# drive-mp1907.net
KiCad netlist of a schematic drawn in Altium Designer
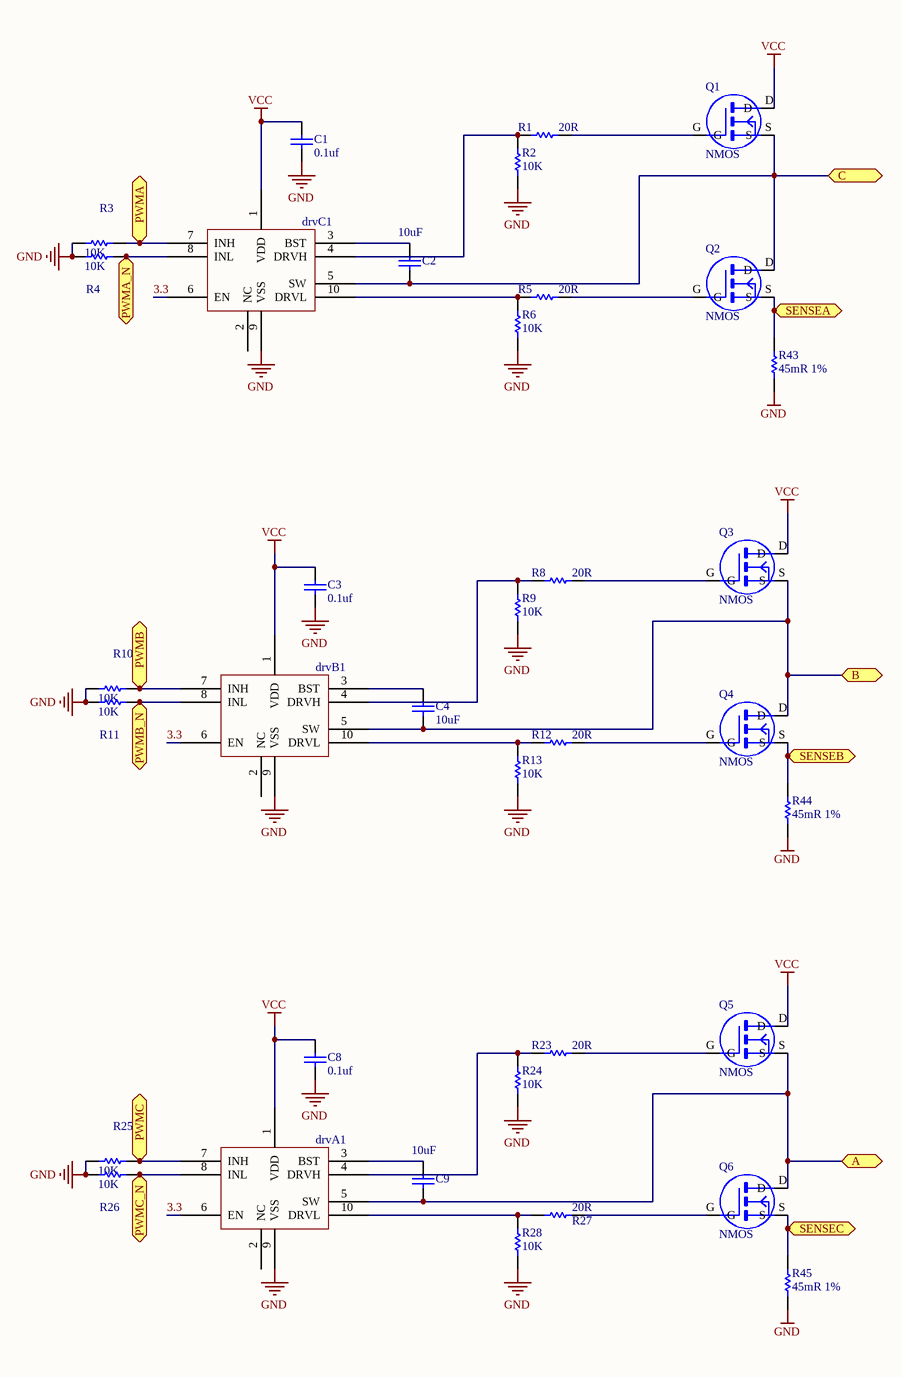
[diagram p0: drive-mp1907.SchDoc]

(export (version "E")
  (design (tool "Eeschema 10.0.6"))
  (components
    (comp (ref "C1")
      (value "0.1uf")
      (footprint "0603")
      (description "Capacitor")
      (fields (field (name "Comment") "Cap") (field (name "PUBLISHER") "Altium Limited"))
      (libsource (lib "PCB_Project") (part "Cap"))
    )
    (comp (ref "C2")
      (value "10uF")
      (footprint "0805")
      (description "Capacitor")
      (fields (field (name "PUBLISHER") "Altium Limited"))
      (libsource (lib "PCB_Project") (part "Cap"))
    )
    (comp (ref "C3")
      (value "0.1uf")
      (footprint "0603")
      (description "Capacitor")
      (fields (field (name "Comment") "Cap") (field (name "PUBLISHER") "Altium Limited"))
      (libsource (lib "PCB_Project") (part "Cap"))
    )
    (comp (ref "C4")
      (value "10uF")
      (footprint "0805")
      (description "Capacitor")
      (fields (field (name "Comment") "Cap") (field (name "PUBLISHER") "Altium Limited"))
      (libsource (lib "PCB_Project") (part "Cap"))
    )
    (comp (ref "C8")
      (value "0.1uf")
      (footprint "0603")
      (description "Capacitor")
      (fields (field (name "Comment") "Cap") (field (name "PUBLISHER") "Altium Limited"))
      (libsource (lib "PCB_Project") (part "Cap"))
    )
    (comp (ref "C9")
      (value "10uF")
      (footprint "0805")
      (description "Capacitor")
      (fields (field (name "PUBLISHER") "Altium Limited"))
      (libsource (lib "PCB_Project") (part "Cap"))
    )
    (comp (ref "drvA1") (value "MP1907") (footprint "MP1907") (libsource (lib "PCB_Project") (part "MP1907")))
    (comp (ref "drvB1") (value "MP1907") (footprint "MP1907") (libsource (lib "PCB_Project") (part "MP1907")))
    (comp (ref "drvC1") (value "MP1907") (footprint "MP1907") (libsource (lib "PCB_Project") (part "MP1907")))
    (comp (ref "Q1") (value "NMOS") (footprint "BSC025N03MS") (libsource (lib "PCB_Project") (part "NMOS")))
    (comp (ref "Q2") (value "NMOS") (footprint "BSC025N03MS") (libsource (lib "PCB_Project") (part "NMOS")))
    (comp (ref "Q3") (value "NMOS") (footprint "BSC025N03MS") (libsource (lib "PCB_Project") (part "NMOS")))
    (comp (ref "Q4") (value "NMOS") (footprint "BSC025N03MS") (libsource (lib "PCB_Project") (part "NMOS")))
    (comp (ref "Q5") (value "NMOS") (footprint "BSC025N03MS") (libsource (lib "PCB_Project") (part "NMOS")))
    (comp (ref "Q6") (value "NMOS") (footprint "BSC025N03MS") (libsource (lib "PCB_Project") (part "NMOS")))
    (comp (ref "R1")
      (value "20R")
      (footprint "0603")
      (description "Resistor")
      (fields (field (name "Comment") "Res1") (field (name "PUBLISHER") "Altium Limited"))
      (libsource (lib "Miscellaneous Devices") (part "Res1"))
    )
    (comp (ref "R2")
      (value "10K")
      (footprint "0603")
      (description "Resistor")
      (fields (field (name "Comment") "Res1") (field (name "PUBLISHER") "Altium Limited"))
      (libsource (lib "Miscellaneous Devices") (part "Res1"))
    )
    (comp (ref "R3")
      (value "10K")
      (footprint "0603")
      (description "Resistor")
      (fields (field (name "Comment") "Res1") (field (name "PUBLISHER") "Altium Limited"))
      (libsource (lib "Miscellaneous Devices") (part "Res1"))
    )
    (comp (ref "R4")
      (value "10K")
      (footprint "0603")
      (description "Resistor")
      (fields (field (name "Comment") "Res1") (field (name "PUBLISHER") "Altium Limited"))
      (libsource (lib "Miscellaneous Devices") (part "Res1"))
    )
    (comp (ref "R5")
      (value "20R")
      (footprint "0603")
      (description "Resistor")
      (fields (field (name "Comment") "Res1") (field (name "PUBLISHER") "Altium Limited"))
      (libsource (lib "Miscellaneous Devices") (part "Res1"))
    )
    (comp (ref "R6")
      (value "10K")
      (footprint "0603")
      (description "Resistor")
      (fields (field (name "Comment") "Res1") (field (name "PUBLISHER") "Altium Limited"))
      (libsource (lib "Miscellaneous Devices") (part "Res1"))
    )
    (comp (ref "R8")
      (value "20R")
      (footprint "0603")
      (description "Resistor")
      (fields (field (name "Comment") "Res1") (field (name "PUBLISHER") "Altium Limited"))
      (libsource (lib "Miscellaneous Devices") (part "Res1"))
    )
    (comp (ref "R9")
      (value "10K")
      (footprint "0603")
      (description "Resistor")
      (fields (field (name "Comment") "Res1") (field (name "PUBLISHER") "Altium Limited"))
      (libsource (lib "Miscellaneous Devices") (part "Res1"))
    )
    (comp (ref "R10")
      (value "10K")
      (footprint "0603")
      (description "Resistor")
      (fields (field (name "Comment") "Res1") (field (name "PUBLISHER") "Altium Limited"))
      (libsource (lib "Miscellaneous Devices") (part "Res1"))
    )
    (comp (ref "R11")
      (value "10K")
      (footprint "0603")
      (description "Resistor")
      (fields (field (name "Comment") "Res1") (field (name "PUBLISHER") "Altium Limited"))
      (libsource (lib "Miscellaneous Devices") (part "Res1"))
    )
    (comp (ref "R12")
      (value "20R")
      (footprint "0603")
      (description "Resistor")
      (fields (field (name "Comment") "Res1") (field (name "PUBLISHER") "Altium Limited"))
      (libsource (lib "Miscellaneous Devices") (part "Res1"))
    )
    (comp (ref "R13")
      (value "10K")
      (footprint "0603")
      (description "Resistor")
      (fields (field (name "Comment") "Res1") (field (name "PUBLISHER") "Altium Limited"))
      (libsource (lib "Miscellaneous Devices") (part "Res1"))
    )
    (comp (ref "R23")
      (value "20R")
      (footprint "0603")
      (description "Resistor")
      (fields (field (name "Comment") "Res1") (field (name "PUBLISHER") "Altium Limited"))
      (libsource (lib "Miscellaneous Devices") (part "Res1"))
    )
    (comp (ref "R24")
      (value "10K")
      (footprint "0603")
      (description "Resistor")
      (fields (field (name "Comment") "Res1") (field (name "PUBLISHER") "Altium Limited"))
      (libsource (lib "Miscellaneous Devices") (part "Res1"))
    )
    (comp (ref "R25")
      (value "10K")
      (footprint "0603")
      (description "Resistor")
      (fields (field (name "Comment") "Res1") (field (name "PUBLISHER") "Altium Limited"))
      (libsource (lib "Miscellaneous Devices") (part "Res1"))
    )
    (comp (ref "R26")
      (value "10K")
      (footprint "0603")
      (description "Resistor")
      (fields (field (name "Comment") "Res1") (field (name "PUBLISHER") "Altium Limited"))
      (libsource (lib "Miscellaneous Devices") (part "Res1"))
    )
    (comp (ref "R27")
      (value "20R")
      (footprint "0603")
      (description "Resistor")
      (fields (field (name "Comment") "Res1") (field (name "PUBLISHER") "Altium Limited"))
      (libsource (lib "Miscellaneous Devices") (part "Res1"))
    )
    (comp (ref "R28")
      (value "10K")
      (footprint "0603")
      (description "Resistor")
      (fields (field (name "Comment") "Res1") (field (name "PUBLISHER") "Altium Limited"))
      (libsource (lib "Miscellaneous Devices") (part "Res1"))
    )
    (comp (ref "R43")
      (value "45mR 1%")
      (footprint "2512")
      (description "Resistor")
      (fields (field (name "PUBLISHER") "Altium Limited"))
      (libsource (lib "Miscellaneous Devices") (part "Res1"))
    )
    (comp (ref "R44")
      (value "45mR 1%")
      (footprint "2512")
      (description "Resistor")
      (fields (field (name "PUBLISHER") "Altium Limited"))
      (libsource (lib "Miscellaneous Devices") (part "Res1"))
    )
    (comp (ref "R45")
      (value "45mR 1%")
      (footprint "2512")
      (description "Resistor")
      (fields (field (name "PUBLISHER") "Altium Limited"))
      (libsource (lib "Miscellaneous Devices") (part "Res1"))
    )
  )
  (nets
    (net (code "1") (name "/3.3") (class "Default")
      (node (ref "drvA1") (pin "6") (pinfunction "EN_6") (pintype "passive"))
      (node (ref "drvB1") (pin "6") (pinfunction "EN_6") (pintype "passive"))
      (node (ref "drvC1") (pin "6") (pinfunction "EN_6") (pintype "passive"))
    )
    (net (code "2") (name "/A") (class "Default")
      (node (ref "C9") (pin "1") (pinfunction "1_1") (pintype "passive"))
      (node (ref "Q5") (pin "S") (pinfunction "S_S") (pintype "passive"))
      (node (ref "Q6") (pin "D") (pinfunction "D_D") (pintype "passive"))
      (node (ref "drvA1") (pin "5") (pinfunction "SW_5") (pintype "passive"))
    )
    (net (code "3") (name "/B") (class "Default")
      (node (ref "C4") (pin "1") (pinfunction "1_1") (pintype "passive"))
      (node (ref "Q3") (pin "S") (pinfunction "S_S") (pintype "passive"))
      (node (ref "Q4") (pin "D") (pinfunction "D_D") (pintype "passive"))
      (node (ref "drvB1") (pin "5") (pinfunction "SW_5") (pintype "passive"))
    )
    (net (code "4") (name "/C") (class "Default")
      (node (ref "C2") (pin "1") (pinfunction "1_1") (pintype "passive"))
      (node (ref "Q1") (pin "S") (pinfunction "S_S") (pintype "passive"))
      (node (ref "Q2") (pin "D") (pinfunction "D_D") (pintype "passive"))
      (node (ref "drvC1") (pin "5") (pinfunction "SW_5") (pintype "passive"))
    )
    (net (code "5") (name "/PWMA") (class "Default")
      (node (ref "R3") (pin "1") (pinfunction "1_1") (pintype "passive"))
      (node (ref "drvC1") (pin "7") (pinfunction "INH_7") (pintype "passive"))
    )
    (net (code "6") (name "/PWMA_N") (class "Default")
      (node (ref "R4") (pin "1") (pinfunction "1_1") (pintype "passive"))
      (node (ref "drvC1") (pin "8") (pinfunction "INL_8") (pintype "passive"))
    )
    (net (code "7") (name "/PWMB") (class "Default")
      (node (ref "R10") (pin "1") (pinfunction "1_1") (pintype "passive"))
      (node (ref "drvB1") (pin "7") (pinfunction "INH_7") (pintype "passive"))
    )
    (net (code "8") (name "/PWMB_N") (class "Default")
      (node (ref "R11") (pin "1") (pinfunction "1_1") (pintype "passive"))
      (node (ref "drvB1") (pin "8") (pinfunction "INL_8") (pintype "passive"))
    )
    (net (code "9") (name "/PWMC") (class "Default")
      (node (ref "R25") (pin "1") (pinfunction "1_1") (pintype "passive"))
      (node (ref "drvA1") (pin "7") (pinfunction "INH_7") (pintype "passive"))
    )
    (net (code "10") (name "/PWMC_N") (class "Default")
      (node (ref "R26") (pin "1") (pinfunction "1_1") (pintype "passive"))
      (node (ref "drvA1") (pin "8") (pinfunction "INL_8") (pintype "passive"))
    )
    (net (code "11") (name "/SENSEA") (class "Default")
      (node (ref "Q2") (pin "S") (pinfunction "S_S") (pintype "passive"))
      (node (ref "R43") (pin "2") (pinfunction "2_2") (pintype "passive"))
    )
    (net (code "12") (name "/SENSEB") (class "Default")
      (node (ref "Q4") (pin "S") (pinfunction "S_S") (pintype "passive"))
      (node (ref "R44") (pin "2") (pinfunction "2_2") (pintype "passive"))
    )
    (net (code "13") (name "/SENSEC") (class "Default")
      (node (ref "Q6") (pin "S") (pinfunction "S_S") (pintype "passive"))
      (node (ref "R45") (pin "2") (pinfunction "2_2") (pintype "passive"))
    )
    (net (code "14") (name "GND") (class "Default")
      (node (ref "C1") (pin "2") (pinfunction "2_2") (pintype "passive"))
      (node (ref "C3") (pin "2") (pinfunction "2_2") (pintype "passive"))
      (node (ref "C8") (pin "2") (pinfunction "2_2") (pintype "passive"))
      (node (ref "R10") (pin "2") (pinfunction "2_2") (pintype "passive"))
      (node (ref "R11") (pin "2") (pinfunction "2_2") (pintype "passive"))
      (node (ref "R13") (pin "2") (pinfunction "2_2") (pintype "passive"))
      (node (ref "R2") (pin "2") (pinfunction "2_2") (pintype "passive"))
      (node (ref "R24") (pin "2") (pinfunction "2_2") (pintype "passive"))
      (node (ref "R25") (pin "2") (pinfunction "2_2") (pintype "passive"))
      (node (ref "R26") (pin "2") (pinfunction "2_2") (pintype "passive"))
      (node (ref "R28") (pin "2") (pinfunction "2_2") (pintype "passive"))
      (node (ref "R3") (pin "2") (pinfunction "2_2") (pintype "passive"))
      (node (ref "R4") (pin "2") (pinfunction "2_2") (pintype "passive"))
      (node (ref "R43") (pin "1") (pinfunction "1_1") (pintype "passive"))
      (node (ref "R44") (pin "1") (pinfunction "1_1") (pintype "passive"))
      (node (ref "R45") (pin "1") (pinfunction "1_1") (pintype "passive"))
      (node (ref "R6") (pin "2") (pinfunction "2_2") (pintype "passive"))
      (node (ref "R9") (pin "2") (pinfunction "2_2") (pintype "passive"))
      (node (ref "drvA1") (pin "9") (pinfunction "VSS_9") (pintype "passive"))
      (node (ref "drvB1") (pin "9") (pinfunction "VSS_9") (pintype "passive"))
      (node (ref "drvC1") (pin "9") (pinfunction "VSS_9") (pintype "passive"))
    )
    (net (code "15") (name "Net-(Q1-PadG)") (class "Default")
      (node (ref "Q1") (pin "G") (pinfunction "G_G") (pintype "passive"))
      (node (ref "R1") (pin "1") (pinfunction "1_1") (pintype "passive"))
    )
    (net (code "16") (name "Net-(Q2-PadG)") (class "Default")
      (node (ref "Q2") (pin "G") (pinfunction "G_G") (pintype "passive"))
      (node (ref "R5") (pin "1") (pinfunction "1_1") (pintype "passive"))
    )
    (net (code "17") (name "Net-(Q3-PadG)") (class "Default")
      (node (ref "Q3") (pin "G") (pinfunction "G_G") (pintype "passive"))
      (node (ref "R8") (pin "1") (pinfunction "1_1") (pintype "passive"))
    )
    (net (code "18") (name "Net-(Q4-PadG)") (class "Default")
      (node (ref "Q4") (pin "G") (pinfunction "G_G") (pintype "passive"))
      (node (ref "R12") (pin "1") (pinfunction "1_1") (pintype "passive"))
    )
    (net (code "19") (name "Net-(Q5-PadG)") (class "Default")
      (node (ref "Q5") (pin "G") (pinfunction "G_G") (pintype "passive"))
      (node (ref "R23") (pin "1") (pinfunction "1_1") (pintype "passive"))
    )
    (net (code "20") (name "Net-(Q6-PadG)") (class "Default")
      (node (ref "Q6") (pin "G") (pinfunction "G_G") (pintype "passive"))
      (node (ref "R27") (pin "1") (pinfunction "1_1") (pintype "passive"))
    )
    (net (code "21") (name "Net-(drvA1-BST)") (class "Default")
      (node (ref "C9") (pin "2") (pinfunction "2_2") (pintype "passive"))
      (node (ref "drvA1") (pin "3") (pinfunction "BST_3") (pintype "passive"))
    )
    (net (code "22") (name "Net-(drvA1-DRVH)") (class "Default")
      (node (ref "R23") (pin "2") (pinfunction "2_2") (pintype "passive"))
      (node (ref "R24") (pin "1") (pinfunction "1_1") (pintype "passive"))
      (node (ref "drvA1") (pin "4") (pinfunction "DRVH_4") (pintype "passive"))
    )
    (net (code "23") (name "Net-(drvA1-DRVL)") (class "Default")
      (node (ref "R27") (pin "2") (pinfunction "2_2") (pintype "passive"))
      (node (ref "R28") (pin "1") (pinfunction "1_1") (pintype "passive"))
      (node (ref "drvA1") (pin "10") (pinfunction "DRVL_10") (pintype "passive"))
    )
    (net (code "24") (name "Net-(drvB1-BST)") (class "Default")
      (node (ref "C4") (pin "2") (pinfunction "2_2") (pintype "passive"))
      (node (ref "drvB1") (pin "3") (pinfunction "BST_3") (pintype "passive"))
    )
    (net (code "25") (name "Net-(drvB1-DRVH)") (class "Default")
      (node (ref "R8") (pin "2") (pinfunction "2_2") (pintype "passive"))
      (node (ref "R9") (pin "1") (pinfunction "1_1") (pintype "passive"))
      (node (ref "drvB1") (pin "4") (pinfunction "DRVH_4") (pintype "passive"))
    )
    (net (code "26") (name "Net-(drvB1-DRVL)") (class "Default")
      (node (ref "R12") (pin "2") (pinfunction "2_2") (pintype "passive"))
      (node (ref "R13") (pin "1") (pinfunction "1_1") (pintype "passive"))
      (node (ref "drvB1") (pin "10") (pinfunction "DRVL_10") (pintype "passive"))
    )
    (net (code "27") (name "Net-(drvC1-BST)") (class "Default")
      (node (ref "C2") (pin "2") (pinfunction "2_2") (pintype "passive"))
      (node (ref "drvC1") (pin "3") (pinfunction "BST_3") (pintype "passive"))
    )
    (net (code "28") (name "Net-(drvC1-DRVH)") (class "Default")
      (node (ref "R1") (pin "2") (pinfunction "2_2") (pintype "passive"))
      (node (ref "R2") (pin "1") (pinfunction "1_1") (pintype "passive"))
      (node (ref "drvC1") (pin "4") (pinfunction "DRVH_4") (pintype "passive"))
    )
    (net (code "29") (name "Net-(drvC1-DRVL)") (class "Default")
      (node (ref "R5") (pin "2") (pinfunction "2_2") (pintype "passive"))
      (node (ref "R6") (pin "1") (pinfunction "1_1") (pintype "passive"))
      (node (ref "drvC1") (pin "10") (pinfunction "DRVL_10") (pintype "passive"))
    )
    (net (code "30") (name "VCC") (class "Default")
      (node (ref "C1") (pin "1") (pinfunction "1_1") (pintype "passive"))
      (node (ref "C3") (pin "1") (pinfunction "1_1") (pintype "passive"))
      (node (ref "C8") (pin "1") (pinfunction "1_1") (pintype "passive"))
      (node (ref "Q1") (pin "D") (pinfunction "D_D") (pintype "passive"))
      (node (ref "Q3") (pin "D") (pinfunction "D_D") (pintype "passive"))
      (node (ref "Q5") (pin "D") (pinfunction "D_D") (pintype "passive"))
      (node (ref "drvA1") (pin "1") (pinfunction "VDD_1") (pintype "passive"))
      (node (ref "drvB1") (pin "1") (pinfunction "VDD_1") (pintype "passive"))
      (node (ref "drvC1") (pin "1") (pinfunction "VDD_1") (pintype "passive"))
    )
    (net (code "31") (name "unconnected-(drvA1-NC-Pad2)") (class "Default")
      (node (ref "drvA1") (pin "2") (pinfunction "NC_2") (pintype "passive"))
    )
    (net (code "32") (name "unconnected-(drvB1-NC-Pad2)") (class "Default")
      (node (ref "drvB1") (pin "2") (pinfunction "NC_2") (pintype "passive"))
    )
    (net (code "33") (name "unconnected-(drvC1-NC-Pad2)") (class "Default")
      (node (ref "drvC1") (pin "2") (pinfunction "NC_2") (pintype "passive"))
    )
  )
)
